# Laptimer.net
KiCad netlist of a schematic drawn in EAGLE
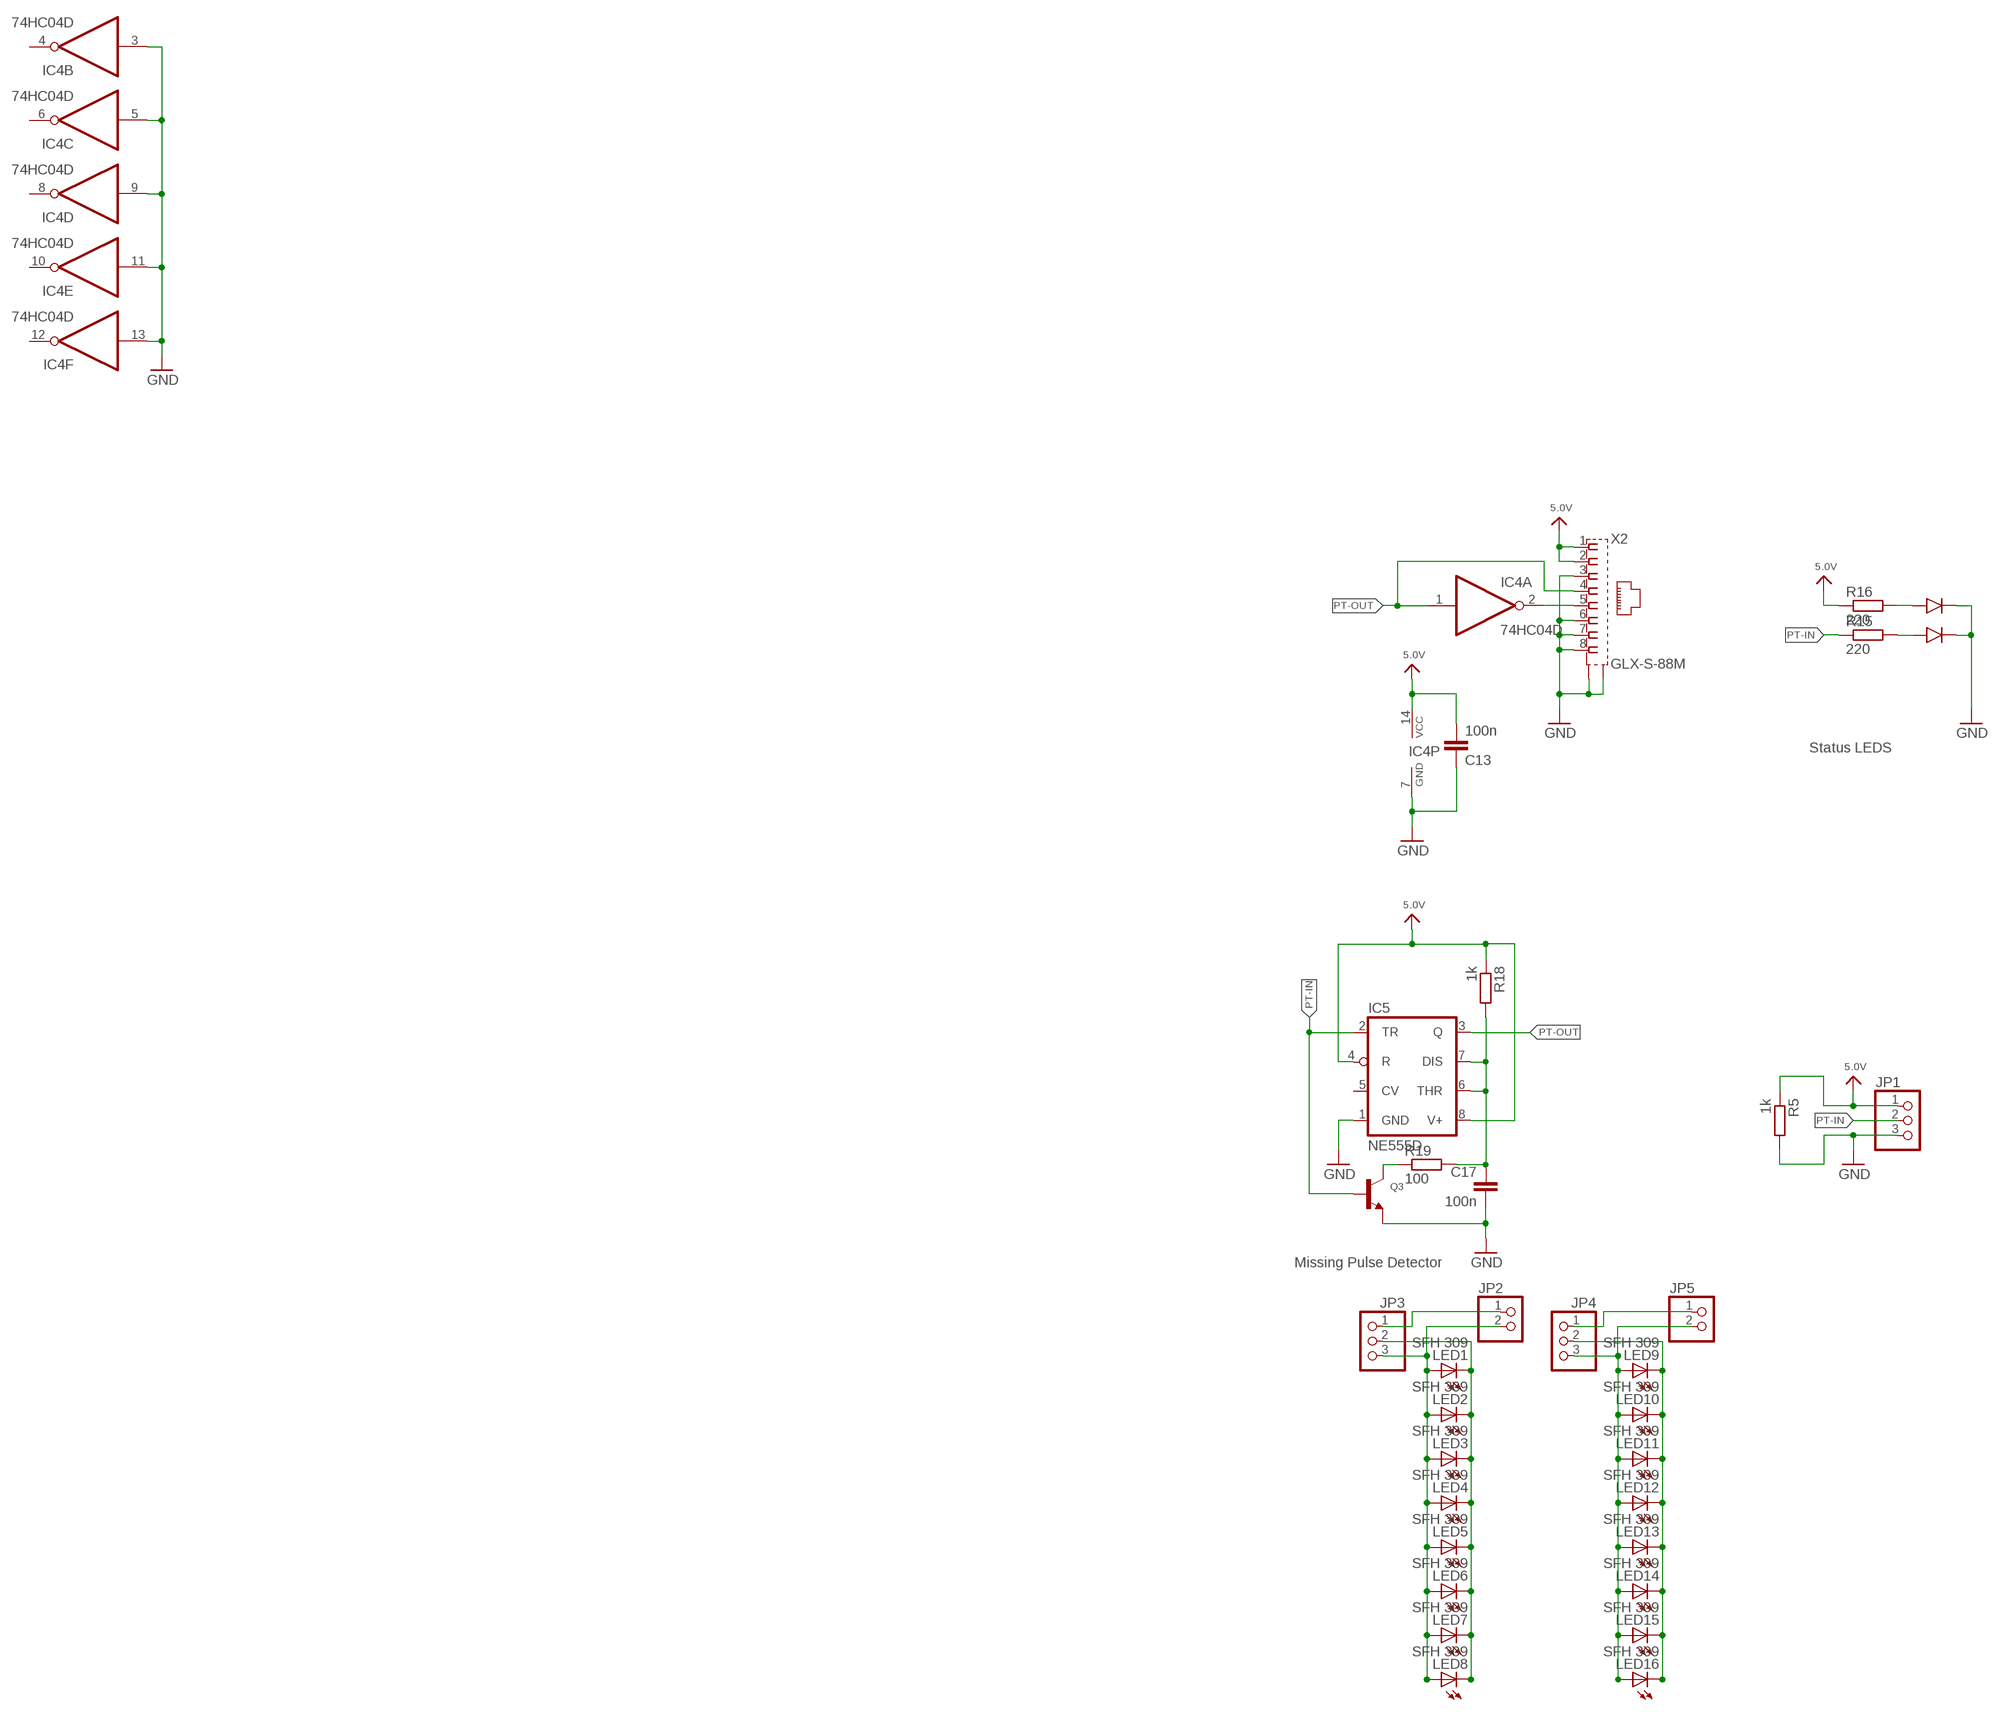
[diagram p0: schematic, sheet 1]

(export (version "E")
  (design (tool "Eeschema 10.0.6"))
  (components
    (comp (ref "C13")
      (value "100n")
      (footprint "eagle-import:C0603K")
      (libsource (lib "eagle-import") (part "C-EUC0603K"))
    )
    (comp (ref "C17")
      (value "100n")
      (footprint "eagle-import:C0603K")
      (libsource (lib "eagle-import") (part "C-EUC0603K"))
    )
    (comp (ref "IC4")
      (value "74HC04D")
      (footprint "eagle-import:SO14")
      (libsource (lib "eagle-import") (part "7404DHC"))
    )
    (comp (ref "IC5")
      (value "NE555D")
      (footprint "eagle-import:SO08")
      (libsource (lib "eagle-import") (part "555DNE"))
    )
    (comp (ref "JP1")
      (value "PINHD-1X3")
      (footprint "eagle-import:1X03")
      (libsource (lib "eagle-import") (part "PINHD-1X3"))
    )
    (comp (ref "JP2")
      (value "HEADER-1X2ROUND")
      (footprint "eagle-import:1X02_ROUND")
      (libsource (lib "eagle-import") (part "HEADER-1X2ROUND"))
    )
    (comp (ref "JP3")
      (value "PINHD-1X3")
      (footprint "eagle-import:1X03")
      (libsource (lib "eagle-import") (part "PINHD-1X3"))
    )
    (comp (ref "JP4")
      (value "PINHD-1X3")
      (footprint "eagle-import:1X03")
      (libsource (lib "eagle-import") (part "PINHD-1X3"))
    )
    (comp (ref "JP5")
      (value "HEADER-1X2ROUND")
      (footprint "eagle-import:1X02_ROUND")
      (libsource (lib "eagle-import") (part "HEADER-1X2ROUND"))
    )
    (comp (ref "LED1")
      (value "SFH 309")
      (footprint "eagle-import:LED3MM")
      (libsource (lib "eagle-import") (part "LED3MM"))
    )
    (comp (ref "LED2")
      (value "SFH 309")
      (footprint "eagle-import:LED3MM")
      (libsource (lib "eagle-import") (part "LED3MM"))
    )
    (comp (ref "LED3")
      (value "SFH 309")
      (footprint "eagle-import:LED3MM")
      (libsource (lib "eagle-import") (part "LED3MM"))
    )
    (comp (ref "LED4")
      (value "SFH 309")
      (footprint "eagle-import:LED3MM")
      (libsource (lib "eagle-import") (part "LED3MM"))
    )
    (comp (ref "LED5")
      (value "SFH 309")
      (footprint "eagle-import:LED3MM")
      (libsource (lib "eagle-import") (part "LED3MM"))
    )
    (comp (ref "LED6")
      (value "SFH 309")
      (footprint "eagle-import:LED3MM")
      (libsource (lib "eagle-import") (part "LED3MM"))
    )
    (comp (ref "LED7")
      (value "SFH 309")
      (footprint "eagle-import:LED3MM")
      (libsource (lib "eagle-import") (part "LED3MM"))
    )
    (comp (ref "LED8")
      (value "SFH 309")
      (footprint "eagle-import:LED3MM")
      (libsource (lib "eagle-import") (part "LED3MM"))
    )
    (comp (ref "LED9")
      (value "SFH 309")
      (footprint "eagle-import:LED3MM")
      (libsource (lib "eagle-import") (part "LED3MM"))
    )
    (comp (ref "LED10")
      (value "SFH 309")
      (footprint "eagle-import:LED3MM")
      (libsource (lib "eagle-import") (part "LED3MM"))
    )
    (comp (ref "LED11")
      (value "SFH 309")
      (footprint "eagle-import:LED3MM")
      (libsource (lib "eagle-import") (part "LED3MM"))
    )
    (comp (ref "LED12")
      (value "SFH 309")
      (footprint "eagle-import:LED3MM")
      (libsource (lib "eagle-import") (part "LED3MM"))
    )
    (comp (ref "LED13")
      (value "SFH 309")
      (footprint "eagle-import:LED3MM")
      (libsource (lib "eagle-import") (part "LED3MM"))
    )
    (comp (ref "LED14")
      (value "SFH 309")
      (footprint "eagle-import:LED3MM")
      (libsource (lib "eagle-import") (part "LED3MM"))
    )
    (comp (ref "LED15")
      (value "SFH 309")
      (footprint "eagle-import:LED3MM")
      (libsource (lib "eagle-import") (part "LED3MM"))
    )
    (comp (ref "LED16")
      (value "SFH 309")
      (footprint "eagle-import:LED3MM")
      (libsource (lib "eagle-import") (part "LED3MM"))
    )
    (comp (ref "Q3")
      (value "TRANSISTOR_NPNWIDE")
      (footprint "eagle-import:SOT23-WIDE")
      (libsource (lib "eagle-import") (part "TRANSISTOR_NPNWIDE"))
    )
    (comp (ref "R5")
      (value "1k")
      (footprint "eagle-import:R0603")
      (libsource (lib "eagle-import") (part "R-EU_R0603"))
    )
    (comp (ref "R15")
      (value "220")
      (footprint "eagle-import:R0603")
      (libsource (lib "eagle-import") (part "R-EU_R0603"))
    )
    (comp (ref "R16")
      (value "220")
      (footprint "eagle-import:R0603")
      (libsource (lib "eagle-import") (part "R-EU_R0603"))
    )
    (comp (ref "R18")
      (value "1k")
      (footprint "eagle-import:R0603")
      (libsource (lib "eagle-import") (part "R-EU_R0603"))
    )
    (comp (ref "R19")
      (value "100")
      (footprint "eagle-import:R0603")
      (libsource (lib "eagle-import") (part "R-EU_R0603"))
    )
    (comp (ref "U$19")
      (value "BI-LEVEL-LED-INDICATOR")
      (footprint "eagle-import:BI-LEVEL-LED-INDICATOR")
      (libsource (lib "eagle-import") (part "BI-LEVEL-LED-INDICATOR"))
    )
    (comp (ref "X2")
      (value "GLX-S-88M")
      (footprint "eagle-import:GLX-S-88M")
      (libsource (lib "eagle-import") (part "GLX-S-88M"))
    )
  )
  (nets
    (net (code "1") (name "5.0V") (class "Default")
      (node (ref "C13") (pin "2") (pinfunction "2_2") (pintype "passive"))
      (node (ref "IC4") (pin "14") (pinfunction "VCC_14") (pintype "power_in"))
      (node (ref "IC5") (pin "4") (pinfunction "R_4") (pintype "input"))
      (node (ref "IC5") (pin "8") (pinfunction "V+_8") (pintype "power_in"))
      (node (ref "JP1") (pin "1") (pinfunction "1_1") (pintype "passive"))
      (node (ref "R16") (pin "1") (pinfunction "1_1") (pintype "passive"))
      (node (ref "R18") (pin "1") (pinfunction "1_1") (pintype "passive"))
      (node (ref "R5") (pin "1") (pinfunction "1_1") (pintype "passive"))
      (node (ref "X2") (pin "1") (pinfunction "1_1") (pintype "passive"))
      (node (ref "X2") (pin "2") (pinfunction "2_2") (pintype "passive"))
    )
    (net (code "2") (name "GND") (class "Default")
      (node (ref "C13") (pin "1") (pinfunction "1_1") (pintype "passive"))
      (node (ref "C17") (pin "2") (pinfunction "2_2") (pintype "passive"))
      (node (ref "IC4") (pin "11") (pinfunction "I_11") (pintype "input"))
      (node (ref "IC4") (pin "13") (pinfunction "I_13") (pintype "input"))
      (node (ref "IC4") (pin "3") (pinfunction "I_3") (pintype "input"))
      (node (ref "IC4") (pin "5") (pinfunction "I_5") (pintype "input"))
      (node (ref "IC4") (pin "7") (pinfunction "GND_7") (pintype "power_in"))
      (node (ref "IC4") (pin "9") (pinfunction "I_9") (pintype "input"))
      (node (ref "IC5") (pin "1") (pinfunction "GND_1") (pintype "power_in"))
      (node (ref "JP1") (pin "3") (pinfunction "3_3") (pintype "passive"))
      (node (ref "Q3") (pin "2") (pinfunction "E_2") (pintype "passive"))
      (node (ref "R5") (pin "2") (pinfunction "2_2") (pintype "passive"))
      (node (ref "U$19") (pin "CATHODE1") (pinfunction "CATHODE1_CATHODE1") (pintype "bidirectional"))
      (node (ref "U$19") (pin "CATHODE2") (pinfunction "CATHODE2_CATHODE2") (pintype "bidirectional"))
      (node (ref "X2") (pin "3") (pinfunction "3_3") (pintype "passive"))
      (node (ref "X2") (pin "6") (pinfunction "6_6") (pintype "passive"))
      (node (ref "X2") (pin "7") (pinfunction "7_7") (pintype "passive"))
      (node (ref "X2") (pin "8") (pinfunction "8_8") (pintype "passive"))
      (node (ref "X2") (pin "S1") (pinfunction "S1_S1") (pintype "passive"))
      (node (ref "X2") (pin "S2") (pinfunction "S2_S2") (pintype "passive"))
    )
    (net (code "3") (name "Net-(IC4A-O)") (class "Default")
      (node (ref "IC4") (pin "2") (pinfunction "O_2") (pintype "output"))
      (node (ref "X2") (pin "5") (pinfunction "5_5") (pintype "passive"))
    )
    (net (code "4") (name "Net-(IC5-DIS)") (class "Default")
      (node (ref "C17") (pin "1") (pinfunction "1_1") (pintype "passive"))
      (node (ref "IC5") (pin "6") (pinfunction "THR_6") (pintype "input"))
      (node (ref "IC5") (pin "7") (pinfunction "DIS_7") (pintype "input"))
      (node (ref "R18") (pin "2") (pinfunction "2_2") (pintype "passive"))
      (node (ref "R19") (pin "2") (pinfunction "2_2") (pintype "passive"))
    )
    (net (code "5") (name "Net-(JP2-Pad1)") (class "Default")
      (node (ref "JP2") (pin "1") (pinfunction "1_1") (pintype "passive"))
      (node (ref "JP3") (pin "1") (pinfunction "1_1") (pintype "passive"))
    )
    (net (code "6") (name "Net-(JP2-Pad2)") (class "Default")
      (node (ref "JP2") (pin "2") (pinfunction "2_2") (pintype "passive"))
      (node (ref "JP3") (pin "3") (pinfunction "3_3") (pintype "passive"))
      (node (ref "LED1") (pin "A") (pinfunction "A_A") (pintype "passive"))
      (node (ref "LED2") (pin "A") (pinfunction "A_A") (pintype "passive"))
      (node (ref "LED3") (pin "A") (pinfunction "A_A") (pintype "passive"))
      (node (ref "LED4") (pin "A") (pinfunction "A_A") (pintype "passive"))
      (node (ref "LED5") (pin "A") (pinfunction "A_A") (pintype "passive"))
      (node (ref "LED6") (pin "A") (pinfunction "A_A") (pintype "passive"))
      (node (ref "LED7") (pin "A") (pinfunction "A_A") (pintype "passive"))
      (node (ref "LED8") (pin "A") (pinfunction "A_A") (pintype "passive"))
    )
    (net (code "7") (name "Net-(JP4-Pad1)") (class "Default")
      (node (ref "JP4") (pin "1") (pinfunction "1_1") (pintype "passive"))
      (node (ref "JP5") (pin "1") (pinfunction "1_1") (pintype "passive"))
    )
    (net (code "8") (name "Net-(JP4-Pad3)") (class "Default")
      (node (ref "JP4") (pin "3") (pinfunction "3_3") (pintype "passive"))
      (node (ref "JP5") (pin "2") (pinfunction "2_2") (pintype "passive"))
      (node (ref "LED10") (pin "A") (pinfunction "A_A") (pintype "passive"))
      (node (ref "LED11") (pin "A") (pinfunction "A_A") (pintype "passive"))
      (node (ref "LED12") (pin "A") (pinfunction "A_A") (pintype "passive"))
      (node (ref "LED13") (pin "A") (pinfunction "A_A") (pintype "passive"))
      (node (ref "LED14") (pin "A") (pinfunction "A_A") (pintype "passive"))
      (node (ref "LED15") (pin "A") (pinfunction "A_A") (pintype "passive"))
      (node (ref "LED16") (pin "A") (pinfunction "A_A") (pintype "passive"))
      (node (ref "LED9") (pin "A") (pinfunction "A_A") (pintype "passive"))
    )
    (net (code "9") (name "Net-(LED1-C)") (class "Default")
      (node (ref "JP3") (pin "2") (pinfunction "2_2") (pintype "passive"))
      (node (ref "LED1") (pin "K") (pinfunction "C_K") (pintype "passive"))
      (node (ref "LED2") (pin "K") (pinfunction "C_K") (pintype "passive"))
      (node (ref "LED3") (pin "K") (pinfunction "C_K") (pintype "passive"))
      (node (ref "LED4") (pin "K") (pinfunction "C_K") (pintype "passive"))
      (node (ref "LED5") (pin "K") (pinfunction "C_K") (pintype "passive"))
      (node (ref "LED6") (pin "K") (pinfunction "C_K") (pintype "passive"))
      (node (ref "LED7") (pin "K") (pinfunction "C_K") (pintype "passive"))
      (node (ref "LED8") (pin "K") (pinfunction "C_K") (pintype "passive"))
    )
    (net (code "10") (name "Net-(LED10-C)") (class "Default")
      (node (ref "JP4") (pin "2") (pinfunction "2_2") (pintype "passive"))
      (node (ref "LED10") (pin "K") (pinfunction "C_K") (pintype "passive"))
      (node (ref "LED11") (pin "K") (pinfunction "C_K") (pintype "passive"))
      (node (ref "LED12") (pin "K") (pinfunction "C_K") (pintype "passive"))
      (node (ref "LED13") (pin "K") (pinfunction "C_K") (pintype "passive"))
      (node (ref "LED14") (pin "K") (pinfunction "C_K") (pintype "passive"))
      (node (ref "LED15") (pin "K") (pinfunction "C_K") (pintype "passive"))
      (node (ref "LED16") (pin "K") (pinfunction "C_K") (pintype "passive"))
      (node (ref "LED9") (pin "K") (pinfunction "C_K") (pintype "passive"))
    )
    (net (code "11") (name "Net-(Q3-C)") (class "Default")
      (node (ref "Q3") (pin "3") (pinfunction "C_3") (pintype "passive"))
      (node (ref "R19") (pin "1") (pinfunction "1_1") (pintype "passive"))
    )
    (net (code "12") (name "Net-(R15-Pad2)") (class "Default")
      (node (ref "R15") (pin "2") (pinfunction "2_2") (pintype "passive"))
      (node (ref "U$19") (pin "ANODE1") (pinfunction "ANODE1_ANODE1") (pintype "bidirectional"))
    )
    (net (code "13") (name "Net-(R16-Pad2)") (class "Default")
      (node (ref "R16") (pin "2") (pinfunction "2_2") (pintype "passive"))
      (node (ref "U$19") (pin "ANODE2") (pinfunction "ANODE2_ANODE2") (pintype "bidirectional"))
    )
    (net (code "14") (name "PT-IN") (class "Default")
      (node (ref "IC5") (pin "2") (pinfunction "TR_2") (pintype "input"))
      (node (ref "JP1") (pin "2") (pinfunction "2_2") (pintype "passive"))
      (node (ref "Q3") (pin "1") (pinfunction "B_1") (pintype "passive"))
      (node (ref "R15") (pin "1") (pinfunction "1_1") (pintype "passive"))
    )
    (net (code "15") (name "PT-OUT") (class "Default")
      (node (ref "IC4") (pin "1") (pinfunction "I_1") (pintype "input"))
      (node (ref "IC5") (pin "3") (pinfunction "Q_3") (pintype "output"))
      (node (ref "X2") (pin "4") (pinfunction "4_4") (pintype "passive"))
    )
    (net (code "16") (name "unconnected-(IC4B-O-Pad4)") (class "Default")
      (node (ref "IC4") (pin "4") (pinfunction "O_4") (pintype "output"))
    )
    (net (code "17") (name "unconnected-(IC4C-O-Pad6)") (class "Default")
      (node (ref "IC4") (pin "6") (pinfunction "O_6") (pintype "output"))
    )
    (net (code "18") (name "unconnected-(IC4D-O-Pad8)") (class "Default")
      (node (ref "IC4") (pin "8") (pinfunction "O_8") (pintype "output"))
    )
    (net (code "19") (name "unconnected-(IC4E-O-Pad10)") (class "Default")
      (node (ref "IC4") (pin "10") (pinfunction "O_10") (pintype "output"))
    )
    (net (code "20") (name "unconnected-(IC4F-O-Pad12)") (class "Default")
      (node (ref "IC4") (pin "12") (pinfunction "O_12") (pintype "output"))
    )
    (net (code "21") (name "unconnected-(IC5-CV-Pad5)") (class "Default")
      (node (ref "IC5") (pin "5") (pinfunction "CV_5") (pintype "input"))
    )
  )
)
